# 04_LMS7002M_Misc.net
KiCad netlist of a schematic drawn in Altium Designer
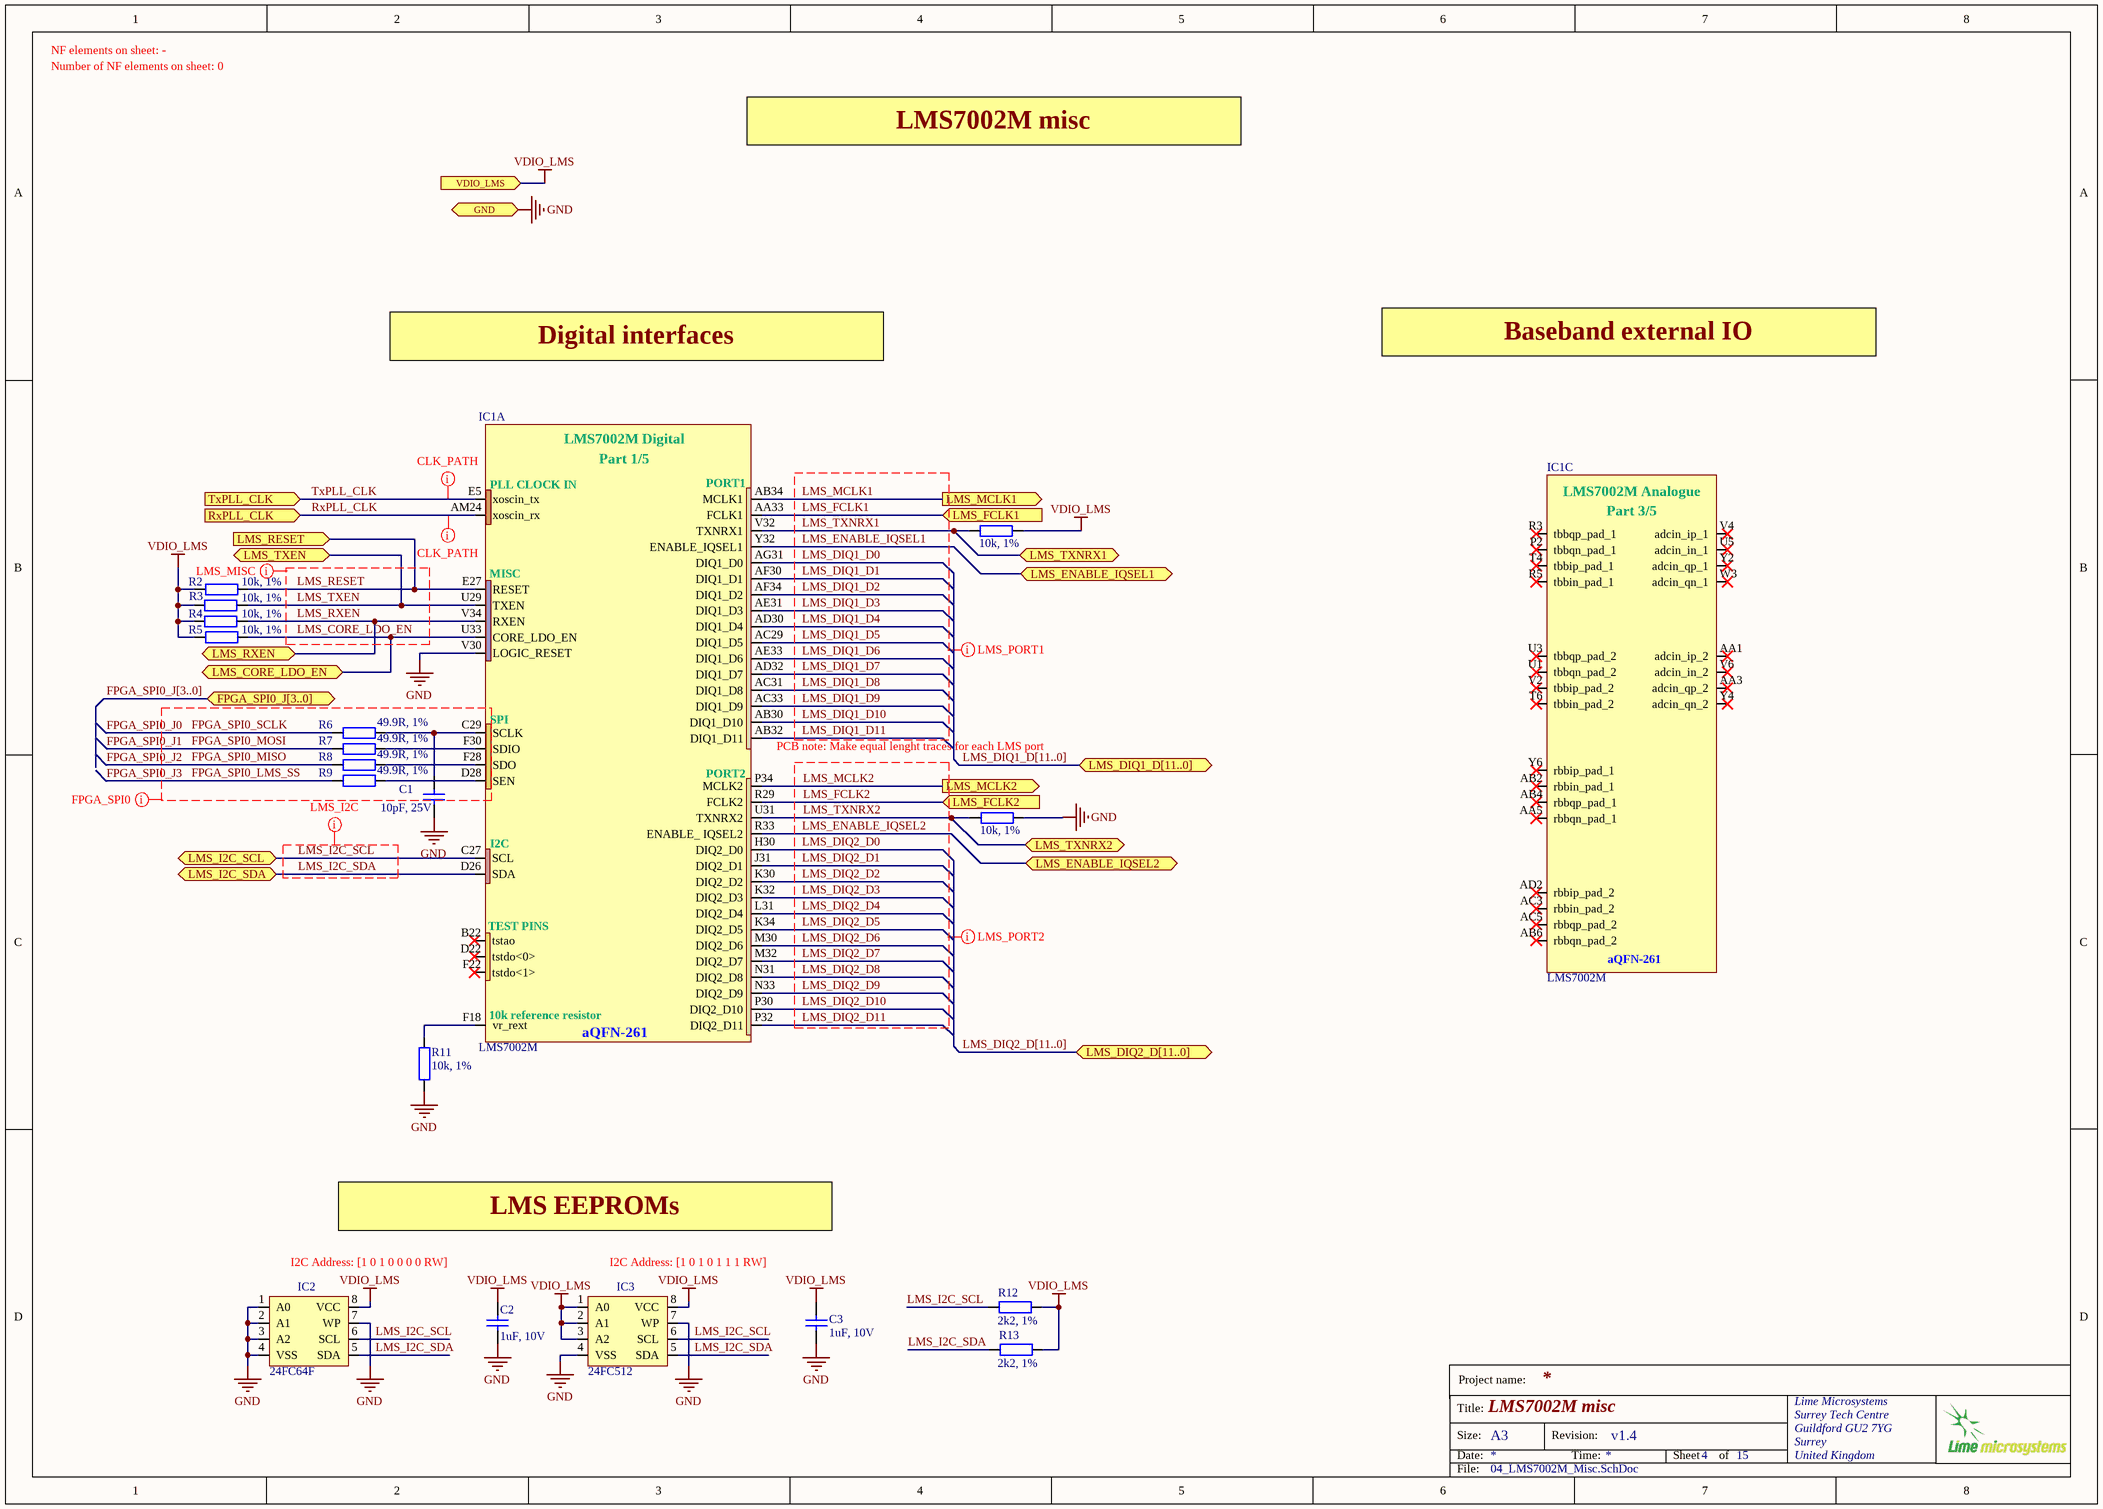
[diagram p0: 04_LMS7002M_Misc.SchDoc]

(export (version "E")
  (design (tool "Eeschema 10.0.6"))
  (components
    (comp (ref "C1")
      (value "10pF, 25V")
      (footprint "CAP0402")
      (fields (field (name "MANUFACTURER") "AVX"))
      (libsource (lib "LimeMicroAltiumLib_schLib") (part "Cap_0402"))
    )
    (comp (ref "C2")
      (value "1uF, 10V")
      (footprint "CAP0402")
      (fields (field (name "MANUFACTURER") "TDK"))
      (libsource (lib "LimeMicroAltiumLib_schLib") (part "Cap_0402"))
    )
    (comp (ref "C3")
      (value "1uF, 10V")
      (footprint "CAP0402")
      (fields (field (name "MANUFACTURER") "TDK"))
      (libsource (lib "LimeMicroAltiumLib_schLib") (part "Cap_0402"))
    )
    (comp (ref "IC1")
      (value "LMS7002M")
      (footprint "LMS7002M_v3")
      (fields (field (name "MANUFACTURER") "Lime Microsystems"))
      (libsource (lib "LimeMicroAltiumLib_schLib") (part "LMS7002M"))
    )
    (comp (ref "IC2")
      (value "24FC64F")
      (footprint "24FC512")
      (fields (field (name "MANUFACTURER") "Microchip Technology"))
      (libsource (lib "LimeMicroAltiumLib_schLib") (part "24FC64F"))
    )
    (comp (ref "IC3")
      (value "24FC512")
      (footprint "24FC512")
      (fields (field (name "MANUFACTURER") "Microchip Technology"))
      (libsource (lib "LimeMicroAltiumLib_schLib") (part "24FC512"))
    )
    (comp (ref "R1")
      (value "10k, 1%")
      (footprint "RES0402")
      (fields (field (name "MANUFACTURER") "Yageo") (field (name "TOLERANCE") "±1%"))
      (libsource (lib "LimeMicroAltiumLib_schLib") (part "Res_0402"))
    )
    (comp (ref "R2")
      (value "10k, 1%")
      (footprint "RES0402")
      (fields (field (name "MANUFACTURER") "Yageo") (field (name "TOLERANCE") "±1%"))
      (libsource (lib "LimeMicroAltiumLib_schLib") (part "Res_0402"))
    )
    (comp (ref "R3")
      (value "10k, 1%")
      (footprint "RES0402")
      (fields (field (name "MANUFACTURER") "Yageo") (field (name "TOLERANCE") "±1%"))
      (libsource (lib "LimeMicroAltiumLib_schLib") (part "Res_0402"))
    )
    (comp (ref "R4")
      (value "10k, 1%")
      (footprint "RES0402")
      (fields (field (name "MANUFACTURER") "Yageo") (field (name "TOLERANCE") "±1%"))
      (libsource (lib "LimeMicroAltiumLib_schLib") (part "Res_0402"))
    )
    (comp (ref "R5")
      (value "10k, 1%")
      (footprint "RES0402")
      (fields (field (name "MANUFACTURER") "Yageo") (field (name "TOLERANCE") "±1%"))
      (libsource (lib "LimeMicroAltiumLib_schLib") (part "Res_0402"))
    )
    (comp (ref "R6")
      (value "49.9R, 1%")
      (footprint "RES0402")
      (fields
        (field (name "TOLERANCE") "±1%")
        (field (name "MANUFACTURER") "Samsung Electro-Mechanics America, Inc.")
        (field (name "MANUFACTURER PART NUMBER") "RC1005F49R9CS")
      )
      (libsource (lib "LimeMicroAltiumLib_schLib") (part "Res_0402"))
    )
    (comp (ref "R7")
      (value "49.9R, 1%")
      (footprint "RES0402")
      (fields
        (field (name "TOLERANCE") "±1%")
        (field (name "MANUFACTURER") "Samsung Electro-Mechanics America, Inc.")
        (field (name "MANUFACTURER PART NUMBER") "RC1005F49R9CS")
      )
      (libsource (lib "LimeMicroAltiumLib_schLib") (part "Res_0402"))
    )
    (comp (ref "R8")
      (value "49.9R, 1%")
      (footprint "RES0402")
      (fields
        (field (name "TOLERANCE") "±1%")
        (field (name "MANUFACTURER") "Samsung Electro-Mechanics America, Inc.")
        (field (name "MANUFACTURER PART NUMBER") "RC1005F49R9CS")
      )
      (libsource (lib "LimeMicroAltiumLib_schLib") (part "Res_0402"))
    )
    (comp (ref "R9")
      (value "49.9R, 1%")
      (footprint "RES0402")
      (fields
        (field (name "TOLERANCE") "±1%")
        (field (name "MANUFACTURER") "Samsung Electro-Mechanics America, Inc.")
        (field (name "MANUFACTURER PART NUMBER") "RC1005F49R9CS")
      )
      (libsource (lib "LimeMicroAltiumLib_schLib") (part "Res_0402"))
    )
    (comp (ref "R10")
      (value "10k, 1%")
      (footprint "RES0402")
      (fields (field (name "MANUFACTURER") "Yageo") (field (name "TOLERANCE") "±1%"))
      (libsource (lib "LimeMicroAltiumLib_schLib") (part "Res_0402"))
    )
    (comp (ref "R11")
      (value "10k, 1%")
      (footprint "RES0402")
      (fields (field (name "MANUFACTURER") "Yageo") (field (name "TOLERANCE") "±1%"))
      (libsource (lib "LimeMicroAltiumLib_schLib") (part "Res_0402"))
    )
    (comp (ref "R12")
      (value "2k2, 1%")
      (footprint "RES0402")
      (fields (field (name "MANUFACTURER") "Stackpole Electronics Inc") (field (name "TOLERANCE") "±1%"))
      (libsource (lib "LimeMicroAltiumLib_schLib") (part "Res_0402"))
    )
    (comp (ref "R13")
      (value "2k2, 1%")
      (footprint "RES0402")
      (fields (field (name "MANUFACTURER") "Stackpole Electronics Inc") (field (name "TOLERANCE") "±1%"))
      (libsource (lib "LimeMicroAltiumLib_schLib") (part "Res_0402"))
    )
  )
  (nets
    (net (code "1") (name "/FPGA_SPI0_J0") (class "Default")
      (node (ref "R6") (pin "2") (pinfunction "2_2") (pintype "passive"))
    )
    (net (code "2") (name "/FPGA_SPI0_J1") (class "Default")
      (node (ref "R7") (pin "2") (pinfunction "2_2") (pintype "passive"))
    )
    (net (code "3") (name "/FPGA_SPI0_J2") (class "Default")
      (node (ref "R8") (pin "2") (pinfunction "2_2") (pintype "passive"))
    )
    (net (code "4") (name "/FPGA_SPI0_J3") (class "Default")
      (node (ref "R9") (pin "2") (pinfunction "2_2") (pintype "passive"))
    )
    (net (code "6") (name "/LMS_CORE_LDO_EN") (class "Default")
      (node (ref "IC1") (pin "U33") (pinfunction "CORE_LDO_EN_U33") (pintype "passive"))
      (node (ref "R5") (pin "1") (pinfunction "1_1") (pintype "passive"))
    )
    (net (code "7") (name "/LMS_DIQ1_D0") (class "Default")
      (node (ref "IC1") (pin "AG31") (pinfunction "DIQ1_D0_AG31") (pintype "passive"))
    )
    (net (code "8") (name "/LMS_DIQ1_D1") (class "Default")
      (node (ref "IC1") (pin "AF30") (pinfunction "DIQ1_D1_AF30") (pintype "passive"))
    )
    (net (code "9") (name "/LMS_DIQ1_D2") (class "Default")
      (node (ref "IC1") (pin "AF34") (pinfunction "DIQ1_D2_AF34") (pintype "passive"))
    )
    (net (code "10") (name "/LMS_DIQ1_D3") (class "Default")
      (node (ref "IC1") (pin "AE31") (pinfunction "DIQ1_D3_AE31") (pintype "passive"))
    )
    (net (code "11") (name "/LMS_DIQ1_D4") (class "Default")
      (node (ref "IC1") (pin "AD30") (pinfunction "DIQ1_D4_AD30") (pintype "passive"))
    )
    (net (code "12") (name "/LMS_DIQ1_D5") (class "Default")
      (node (ref "IC1") (pin "AC29") (pinfunction "DIQ1_D5_AC29") (pintype "passive"))
    )
    (net (code "13") (name "/LMS_DIQ1_D6") (class "Default")
      (node (ref "IC1") (pin "AE33") (pinfunction "DIQ1_D6_AE33") (pintype "passive"))
    )
    (net (code "14") (name "/LMS_DIQ1_D7") (class "Default")
      (node (ref "IC1") (pin "AD32") (pinfunction "DIQ1_D7_AD32") (pintype "passive"))
    )
    (net (code "15") (name "/LMS_DIQ1_D8") (class "Default")
      (node (ref "IC1") (pin "AC31") (pinfunction "DIQ1_D8_AC31") (pintype "passive"))
    )
    (net (code "16") (name "/LMS_DIQ1_D9") (class "Default")
      (node (ref "IC1") (pin "AC33") (pinfunction "DIQ1_D9_AC33") (pintype "passive"))
    )
    (net (code "17") (name "/LMS_DIQ1_D10") (class "Default")
      (node (ref "IC1") (pin "AB30") (pinfunction "DIQ1_D10_AB30") (pintype "passive"))
    )
    (net (code "18") (name "/LMS_DIQ1_D11") (class "Default")
      (node (ref "IC1") (pin "AB32") (pinfunction "DIQ1_D11_AB32") (pintype "passive"))
    )
    (net (code "20") (name "/LMS_DIQ2_D0") (class "Default")
      (node (ref "IC1") (pin "H30") (pinfunction "DIQ2_D0_H30") (pintype "passive"))
    )
    (net (code "21") (name "/LMS_DIQ2_D1") (class "Default")
      (node (ref "IC1") (pin "J31") (pinfunction "DIQ2_D1_J31") (pintype "passive"))
    )
    (net (code "22") (name "/LMS_DIQ2_D2") (class "Default")
      (node (ref "IC1") (pin "K30") (pinfunction "DIQ2_D2_K30") (pintype "passive"))
    )
    (net (code "23") (name "/LMS_DIQ2_D3") (class "Default")
      (node (ref "IC1") (pin "K32") (pinfunction "DIQ2_D3_K32") (pintype "passive"))
    )
    (net (code "24") (name "/LMS_DIQ2_D4") (class "Default")
      (node (ref "IC1") (pin "L31") (pinfunction "DIQ2_D4_L31") (pintype "passive"))
    )
    (net (code "25") (name "/LMS_DIQ2_D5") (class "Default")
      (node (ref "IC1") (pin "K34") (pinfunction "DIQ2_D5_K34") (pintype "passive"))
    )
    (net (code "26") (name "/LMS_DIQ2_D6") (class "Default")
      (node (ref "IC1") (pin "M30") (pinfunction "DIQ2_D6_M30") (pintype "passive"))
    )
    (net (code "27") (name "/LMS_DIQ2_D7") (class "Default")
      (node (ref "IC1") (pin "M32") (pinfunction "DIQ2_D7_M32") (pintype "passive"))
    )
    (net (code "28") (name "/LMS_DIQ2_D8") (class "Default")
      (node (ref "IC1") (pin "N31") (pinfunction "DIQ2_D8_N31") (pintype "passive"))
    )
    (net (code "29") (name "/LMS_DIQ2_D9") (class "Default")
      (node (ref "IC1") (pin "N33") (pinfunction "DIQ2_D9_N33") (pintype "passive"))
    )
    (net (code "30") (name "/LMS_DIQ2_D10") (class "Default")
      (node (ref "IC1") (pin "P30") (pinfunction "DIQ2_D10_P30") (pintype "passive"))
    )
    (net (code "31") (name "/LMS_DIQ2_D11") (class "Default")
      (node (ref "IC1") (pin "P32") (pinfunction "DIQ2_D11_P32") (pintype "passive"))
    )
    (net (code "33") (name "/LMS_ENABLE_IQSEL1") (class "Default")
      (node (ref "IC1") (pin "Y32") (pinfunction "ENABLE_IQSEL1_Y32") (pintype "passive"))
    )
    (net (code "34") (name "/LMS_ENABLE_IQSEL2") (class "Default")
      (node (ref "IC1") (pin "R33") (pinfunction "ENABLE__IQSEL2_R33") (pintype "passive"))
    )
    (net (code "35") (name "/LMS_FCLK1") (class "Default")
      (node (ref "IC1") (pin "AA33") (pinfunction "FCLK1_AA33") (pintype "passive"))
    )
    (net (code "36") (name "/LMS_FCLK2") (class "Default")
      (node (ref "IC1") (pin "R29") (pinfunction "FCLK2_R29") (pintype "passive"))
    )
    (net (code "37") (name "/LMS_I2C_SCL") (class "Default")
      (node (ref "IC1") (pin "C27") (pinfunction "SCL_C27") (pintype "passive"))
      (node (ref "IC2") (pin "6") (pinfunction "SCL_6") (pintype "passive"))
      (node (ref "IC3") (pin "6") (pinfunction "SCL_6") (pintype "passive"))
      (node (ref "R12") (pin "2") (pinfunction "2_2") (pintype "passive"))
    )
    (net (code "38") (name "/LMS_I2C_SDA") (class "Default")
      (node (ref "IC1") (pin "D26") (pinfunction "SDA_D26") (pintype "passive"))
      (node (ref "IC2") (pin "5") (pinfunction "SDA_5") (pintype "passive"))
      (node (ref "IC3") (pin "5") (pinfunction "SDA_5") (pintype "passive"))
      (node (ref "R13") (pin "2") (pinfunction "2_2") (pintype "passive"))
    )
    (net (code "39") (name "/LMS_MCLK1") (class "Default")
      (node (ref "IC1") (pin "AB34") (pinfunction "MCLK1_AB34") (pintype "passive"))
    )
    (net (code "40") (name "/LMS_MCLK2") (class "Default")
      (node (ref "IC1") (pin "P34") (pinfunction "MCLK2_P34") (pintype "passive"))
    )
    (net (code "41") (name "/LMS_RESET") (class "Default")
      (node (ref "IC1") (pin "E27") (pinfunction "RESET_E27") (pintype "passive"))
      (node (ref "R2") (pin "1") (pinfunction "1_1") (pintype "passive"))
    )
    (net (code "42") (name "/LMS_RXEN") (class "Default")
      (node (ref "IC1") (pin "V34") (pinfunction "RXEN_V34") (pintype "passive"))
      (node (ref "R4") (pin "2") (pinfunction "2_2") (pintype "passive"))
    )
    (net (code "43") (name "/LMS_TXEN") (class "Default")
      (node (ref "IC1") (pin "U29") (pinfunction "TXEN_U29") (pintype "passive"))
      (node (ref "R3") (pin "2") (pinfunction "2_2") (pintype "passive"))
    )
    (net (code "44") (name "/LMS_TXNRX1") (class "Default")
      (node (ref "IC1") (pin "V32") (pinfunction "TXNRX1_V32") (pintype "passive"))
      (node (ref "R1") (pin "1") (pinfunction "1_1") (pintype "passive"))
    )
    (net (code "45") (name "/LMS_TXNRX2") (class "Default")
      (node (ref "IC1") (pin "U31") (pinfunction "TXNRX2_U31") (pintype "passive"))
      (node (ref "R10") (pin "2") (pinfunction "2_2") (pintype "passive"))
    )
    (net (code "46") (name "/RxPLL_CLK") (class "Default")
      (node (ref "IC1") (pin "AM24") (pinfunction "xoscin_rx_AM24") (pintype "passive"))
    )
    (net (code "47") (name "/TxPLL_CLK") (class "Default")
      (node (ref "IC1") (pin "E5") (pinfunction "xoscin_tx_E5") (pintype "passive"))
    )
    (net (code "48") (name "GND") (class "Default")
      (node (ref "C1") (pin "2") (pinfunction "2_2") (pintype "passive"))
      (node (ref "C2") (pin "2") (pinfunction "2_2") (pintype "passive"))
      (node (ref "C3") (pin "1") (pinfunction "1_1") (pintype "passive"))
      (node (ref "IC1") (pin "V30") (pinfunction "LOGIC_RESET_V30") (pintype "passive"))
      (node (ref "IC2") (pin "1") (pinfunction "A0_1") (pintype "passive"))
      (node (ref "IC2") (pin "2") (pinfunction "A1_2") (pintype "passive"))
      (node (ref "IC2") (pin "3") (pinfunction "A2_3") (pintype "passive"))
      (node (ref "IC2") (pin "4") (pinfunction "VSS_4") (pintype "passive"))
      (node (ref "IC2") (pin "7") (pinfunction "WP_7") (pintype "passive"))
      (node (ref "IC3") (pin "4") (pinfunction "VSS_4") (pintype "passive"))
      (node (ref "IC3") (pin "7") (pinfunction "WP_7") (pintype "passive"))
      (node (ref "R10") (pin "1") (pinfunction "1_1") (pintype "passive"))
      (node (ref "R11") (pin "2") (pinfunction "2_2") (pintype "passive"))
    )
    (net (code "49") (name "Net-(IC1A-SCLK)") (class "Default")
      (node (ref "C1") (pin "1") (pinfunction "1_1") (pintype "passive"))
      (node (ref "IC1") (pin "C29") (pinfunction "SCLK_C29") (pintype "passive"))
      (node (ref "R6") (pin "1") (pinfunction "1_1") (pintype "passive"))
    )
    (net (code "50") (name "Net-(IC1A-SDIO)") (class "Default")
      (node (ref "IC1") (pin "F30") (pinfunction "SDIO_F30") (pintype "passive"))
      (node (ref "R7") (pin "1") (pinfunction "1_1") (pintype "passive"))
    )
    (net (code "51") (name "Net-(IC1A-SDO)") (class "Default")
      (node (ref "IC1") (pin "F28") (pinfunction "SDO_F28") (pintype "passive"))
      (node (ref "R8") (pin "1") (pinfunction "1_1") (pintype "passive"))
    )
    (net (code "52") (name "Net-(IC1A-SEN)") (class "Default")
      (node (ref "IC1") (pin "D28") (pinfunction "SEN_D28") (pintype "passive"))
      (node (ref "R9") (pin "1") (pinfunction "1_1") (pintype "passive"))
    )
    (net (code "53") (name "Net-(IC1A-vr_rext)") (class "Default")
      (node (ref "IC1") (pin "F18") (pinfunction "vr_rext_F18") (pintype "passive"))
      (node (ref "R11") (pin "1") (pinfunction "1_1") (pintype "passive"))
    )
    (net (code "54") (name "VDIO_LMS") (class "Default")
      (node (ref "C2") (pin "1") (pinfunction "1_1") (pintype "passive"))
      (node (ref "C3") (pin "2") (pinfunction "2_2") (pintype "passive"))
      (node (ref "IC2") (pin "8") (pinfunction "VCC_8") (pintype "passive"))
      (node (ref "IC3") (pin "1") (pinfunction "A0_1") (pintype "passive"))
      (node (ref "IC3") (pin "2") (pinfunction "A1_2") (pintype "passive"))
      (node (ref "IC3") (pin "3") (pinfunction "A2_3") (pintype "passive"))
      (node (ref "IC3") (pin "8") (pinfunction "VCC_8") (pintype "passive"))
      (node (ref "R1") (pin "2") (pinfunction "2_2") (pintype "passive"))
      (node (ref "R12") (pin "1") (pinfunction "1_1") (pintype "passive"))
      (node (ref "R13") (pin "1") (pinfunction "1_1") (pintype "passive"))
      (node (ref "R2") (pin "2") (pinfunction "2_2") (pintype "passive"))
      (node (ref "R3") (pin "1") (pinfunction "1_1") (pintype "passive"))
      (node (ref "R4") (pin "1") (pinfunction "1_1") (pintype "passive"))
      (node (ref "R5") (pin "2") (pinfunction "2_2") (pintype "passive"))
    )
    (net (code "55") (name "unconnected-(IC1A-tstao-PadB22)") (class "Default")
      (node (ref "IC1") (pin "B22") (pinfunction "tstao_B22") (pintype "passive+no_connect"))
    )
    (net (code "56") (name "unconnected-(IC1A-tstdo<0>-PadD22)") (class "Default")
      (node (ref "IC1") (pin "D22") (pinfunction "tstdo<0>_D22") (pintype "passive+no_connect"))
    )
    (net (code "57") (name "unconnected-(IC1A-tstdo<1>-PadF22)") (class "Default")
      (node (ref "IC1") (pin "F22") (pinfunction "tstdo<1>_F22") (pintype "passive+no_connect"))
    )
    (net (code "58") (name "unconnected-(IC1C-adcin_in_1-PadU5)") (class "Default")
      (node (ref "IC1") (pin "U5") (pinfunction "adcin_in_1_U5") (pintype "passive+no_connect"))
    )
    (net (code "59") (name "unconnected-(IC1C-adcin_in_2-PadV6)") (class "Default")
      (node (ref "IC1") (pin "V6") (pinfunction "adcin_in_2_V6") (pintype "passive+no_connect"))
    )
    (net (code "60") (name "unconnected-(IC1C-adcin_ip_1-PadV4)") (class "Default")
      (node (ref "IC1") (pin "V4") (pinfunction "adcin_ip_1_V4") (pintype "passive+no_connect"))
    )
    (net (code "61") (name "unconnected-(IC1C-adcin_ip_2-PadAA1)") (class "Default")
      (node (ref "IC1") (pin "AA1") (pinfunction "adcin_ip_2_AA1") (pintype "passive+no_connect"))
    )
    (net (code "62") (name "unconnected-(IC1C-adcin_qn_1-PadW3)") (class "Default")
      (node (ref "IC1") (pin "W3") (pinfunction "adcin_qn_1_W3") (pintype "passive+no_connect"))
    )
    (net (code "63") (name "unconnected-(IC1C-adcin_qn_2-PadY4)") (class "Default")
      (node (ref "IC1") (pin "Y4") (pinfunction "adcin_qn_2_Y4") (pintype "passive+no_connect"))
    )
    (net (code "64") (name "unconnected-(IC1C-adcin_qp_1-PadY2)") (class "Default")
      (node (ref "IC1") (pin "Y2") (pinfunction "adcin_qp_1_Y2") (pintype "passive+no_connect"))
    )
    (net (code "65") (name "unconnected-(IC1C-adcin_qp_2-PadAA3)") (class "Default")
      (node (ref "IC1") (pin "AA3") (pinfunction "adcin_qp_2_AA3") (pintype "passive+no_connect"))
    )
    (net (code "66") (name "unconnected-(IC1C-rbbin_pad_1-PadAB2)") (class "Default")
      (node (ref "IC1") (pin "AB2") (pinfunction "rbbin_pad_1_AB2") (pintype "passive+no_connect"))
    )
    (net (code "67") (name "unconnected-(IC1C-rbbin_pad_2-PadAC3)") (class "Default")
      (node (ref "IC1") (pin "AC3") (pinfunction "rbbin_pad_2_AC3") (pintype "passive+no_connect"))
    )
    (net (code "68") (name "unconnected-(IC1C-rbbip_pad_1-PadY6)") (class "Default")
      (node (ref "IC1") (pin "Y6") (pinfunction "rbbip_pad_1_Y6") (pintype "passive+no_connect"))
    )
    (net (code "69") (name "unconnected-(IC1C-rbbip_pad_2-PadAD2)") (class "Default")
      (node (ref "IC1") (pin "AD2") (pinfunction "rbbip_pad_2_AD2") (pintype "passive+no_connect"))
    )
    (net (code "70") (name "unconnected-(IC1C-rbbqn_pad_1-PadAA5)") (class "Default")
      (node (ref "IC1") (pin "AA5") (pinfunction "rbbqn_pad_1_AA5") (pintype "passive+no_connect"))
    )
    (net (code "71") (name "unconnected-(IC1C-rbbqn_pad_2-PadAB6)") (class "Default")
      (node (ref "IC1") (pin "AB6") (pinfunction "rbbqn_pad_2_AB6") (pintype "passive+no_connect"))
    )
    (net (code "72") (name "unconnected-(IC1C-rbbqp_pad_1-PadAB4)") (class "Default")
      (node (ref "IC1") (pin "AB4") (pinfunction "rbbqp_pad_1_AB4") (pintype "passive+no_connect"))
    )
    (net (code "73") (name "unconnected-(IC1C-rbbqp_pad_2-PadAC5)") (class "Default")
      (node (ref "IC1") (pin "AC5") (pinfunction "rbbqp_pad_2_AC5") (pintype "passive+no_connect"))
    )
    (net (code "74") (name "unconnected-(IC1C-tbbin_pad_1-PadR5)") (class "Default")
      (node (ref "IC1") (pin "R5") (pinfunction "tbbin_pad_1_R5") (pintype "passive+no_connect"))
    )
    (net (code "75") (name "unconnected-(IC1C-tbbin_pad_2-PadT6)") (class "Default")
      (node (ref "IC1") (pin "T6") (pinfunction "tbbin_pad_2_T6") (pintype "passive+no_connect"))
    )
    (net (code "76") (name "unconnected-(IC1C-tbbip_pad_1-PadT4)") (class "Default")
      (node (ref "IC1") (pin "T4") (pinfunction "tbbip_pad_1_T4") (pintype "passive+no_connect"))
    )
    (net (code "77") (name "unconnected-(IC1C-tbbip_pad_2-PadV2)") (class "Default")
      (node (ref "IC1") (pin "V2") (pinfunction "tbbip_pad_2_V2") (pintype "passive+no_connect"))
    )
    (net (code "78") (name "unconnected-(IC1C-tbbqn_pad_1-PadP2)") (class "Default")
      (node (ref "IC1") (pin "P2") (pinfunction "tbbqn_pad_1_P2") (pintype "passive+no_connect"))
    )
    (net (code "79") (name "unconnected-(IC1C-tbbqn_pad_2-PadU1)") (class "Default")
      (node (ref "IC1") (pin "U1") (pinfunction "tbbqn_pad_2_U1") (pintype "passive+no_connect"))
    )
    (net (code "80") (name "unconnected-(IC1C-tbbqp_pad_1-PadR3)") (class "Default")
      (node (ref "IC1") (pin "R3") (pinfunction "tbbqp_pad_1_R3") (pintype "passive+no_connect"))
    )
    (net (code "81") (name "unconnected-(IC1C-tbbqp_pad_2-PadU3)") (class "Default")
      (node (ref "IC1") (pin "U3") (pinfunction "tbbqp_pad_2_U3") (pintype "passive+no_connect"))
    )
  )
)
